# Sheet1.net
KiCad netlist of a schematic drawn in Altium Designer
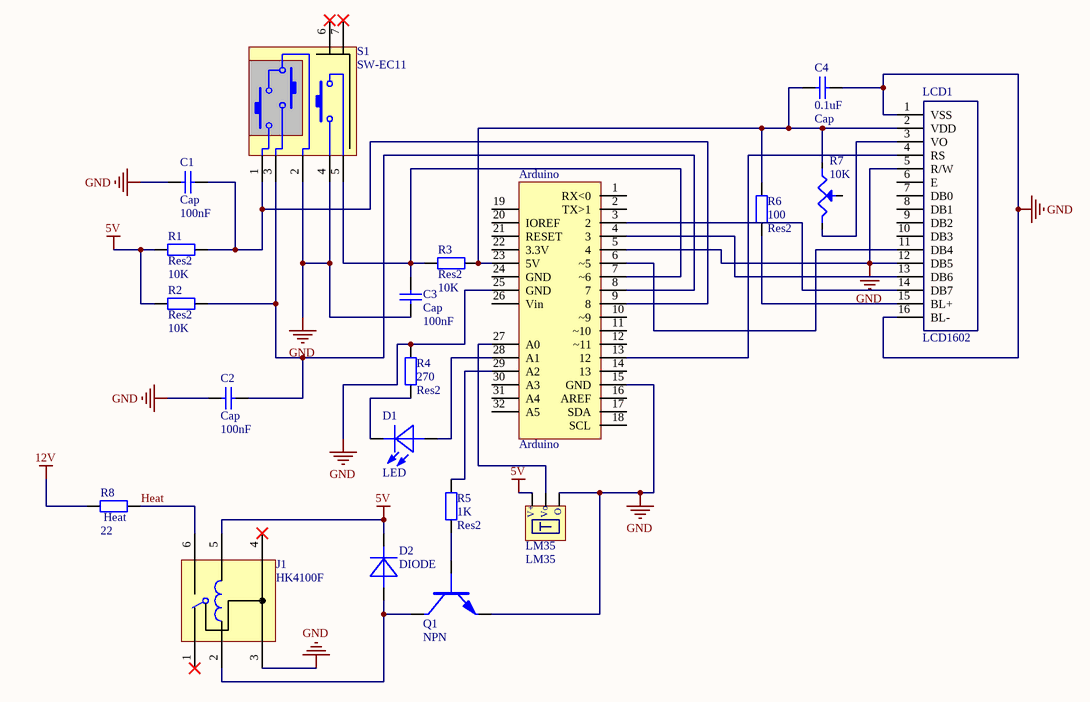
[diagram p0: Sheet1.SchDoc]

(export (version "E")
  (design (tool "Eeschema 10.0.6"))
  (components
    (comp (ref "Arduino")
      (value "Arduino")
      (footprint "Arduino-UNO")
      (libsource (lib "LixhSch") (part "Arduino-UNO"))
    )
    (comp (ref "C1")
      (value "Cap")
      (footprint "RAD-0.3")
      (description "Capacitor")
      (fields (field (name "ALTIUM_VALUE") "100nF") (field (name "PUBLISHER") "Altium Limited"))
      (libsource (lib "Miscellaneous Devices") (part "Cap"))
    )
    (comp (ref "C2")
      (value "Cap")
      (footprint "RAD-0.3")
      (description "Capacitor")
      (fields (field (name "ALTIUM_VALUE") "100nF") (field (name "PUBLISHER") "Altium Limited"))
      (libsource (lib "Miscellaneous Devices") (part "Cap"))
    )
    (comp (ref "C3")
      (value "Cap")
      (footprint "RAD-0.3")
      (description "Capacitor")
      (fields (field (name "ALTIUM_VALUE") "100nF") (field (name "PUBLISHER") "Altium Limited"))
      (libsource (lib "Miscellaneous Devices") (part "Cap"))
    )
    (comp (ref "C4")
      (value "Cap")
      (footprint "RAD-0.3")
      (description "Capacitor")
      (fields (field (name "ALTIUM_VALUE") "0.1uF") (field (name "PUBLISHER") "Altium Limited"))
      (libsource (lib "Miscellaneous Devices") (part "Cap"))
    )
    (comp (ref "D1")
      (value "LED")
      (footprint "LEDLXH-5")
      (description "发光二极管")
      (libsource (lib "LixhSch") (part "LEDLXH"))
    )
    (comp (ref "D2")
      (value "DIODE")
      (footprint "DIODE-4")
      (description "Diode")
      (libsource (lib "LixhSch") (part "DIODELXH"))
    )
    (comp (ref "J1")
      (value "HK4100F")
      (footprint "HK4100F")
      (description "单刀双掷继电器")
      (libsource (lib "Fszhang") (part "HK4100F"))
    )
    (comp (ref "LCD1") (value "LCD1602") (footprint "LCD1602") (libsource (lib "LCD") (part "LCD1602")))
    (comp (ref "LM35")
      (value "LM35")
      (footprint "LM35")
      (description "LM35温度传感器")
      (libsource (lib "LixhSch") (part "LM35"))
    )
    (comp (ref "Q1")
      (value "NPN")
      (footprint "NPN")
      (description "NPN Transistor")
      (libsource (lib "LixhSch") (part "NPNLXH"))
    )
    (comp (ref "R1")
      (value "Res2")
      (footprint "AXIAL-0.4")
      (description "Resistor")
      (fields (field (name "ALTIUM_VALUE") "10K") (field (name "PUBLISHER") "Altium Limited"))
      (libsource (lib "") (part "Res2_1"))
    )
    (comp (ref "R2")
      (value "Res2")
      (footprint "AXIAL-0.4")
      (description "Resistor")
      (fields (field (name "ALTIUM_VALUE") "10K") (field (name "PUBLISHER") "Altium Limited"))
      (libsource (lib "") (part "Res2_1"))
    )
    (comp (ref "R3")
      (value "Res2")
      (footprint "AXIAL-0.4")
      (description "Resistor")
      (fields (field (name "ALTIUM_VALUE") "10K") (field (name "PUBLISHER") "Altium Limited"))
      (libsource (lib "") (part "Res2_1"))
    )
    (comp (ref "R4")
      (value "Res2")
      (footprint "AXIAL-0.4")
      (description "Resistor")
      (fields (field (name "ALTIUM_VALUE") "270") (field (name "PUBLISHER") "Altium Limited"))
      (libsource (lib "Miscellaneous Devices") (part "Res2"))
    )
    (comp (ref "R5")
      (value "Res2")
      (footprint "AXIAL-0.4")
      (description "Resistor")
      (fields (field (name "ALTIUM_VALUE") "1K") (field (name "PUBLISHER") "Altium Limited"))
      (libsource (lib "Miscellaneous Devices") (part "Res2"))
    )
    (comp (ref "R6")
      (value "Res2")
      (footprint "AXIAL-0.4")
      (description "Resistor")
      (fields (field (name "ALTIUM_VALUE") "100") (field (name "PUBLISHER") "Altium Limited"))
      (libsource (lib "Miscellaneous Devices") (part "Res2"))
    )
    (comp (ref "R7")
      (value "10K")
      (footprint "VR-5")
      (description "Potentiometer")
      (libsource (lib "Miscellaneous Devices") (part "POT1"))
    )
    (comp (ref "R8")
      (value "Heat")
      (footprint "AXIAL-0.4")
      (description "Resistor")
      (fields (field (name "ALTIUM_VALUE") "22") (field (name "PUBLISHER") "Altium Limited"))
      (libsource (lib "") (part "Res2_2"))
    )
    (comp (ref "S1")
      (value "SW-EC11")
      (footprint "EC11")
      (description "旋转编码开关")
      (fields (field (name "PUBLISHER") "Altium Limited"))
      (libsource (lib "LixhSch") (part "SW-EC11"))
    )
  )
  (nets
    (net (code "1") (name "/Heat") (class "Default")
      (node (ref "J1") (pin "6") (pinfunction "6_6") (pintype "passive"))
      (node (ref "R8") (pin "1") (pinfunction "1_1") (pintype "passive"))
    )
    (net (code "2") (name "5V") (class "Default")
      (node (ref "D2") (pin "2") (pinfunction "K_2") (pintype "passive"))
      (node (ref "J1") (pin "5") (pinfunction "5_5") (pintype "passive"))
      (node (ref "LM35") (pin "1") (pinfunction "1_1") (pintype "power_in"))
      (node (ref "R1") (pin "1") (pinfunction "1_1") (pintype "passive"))
      (node (ref "R2") (pin "1") (pinfunction "1_1") (pintype "passive"))
    )
    (net (code "3") (name "12V") (class "Default")
      (node (ref "R8") (pin "2") (pinfunction "2_2") (pintype "passive"))
    )
    (net (code "4") (name "GND") (class "Default")
      (node (ref "Arduino") (pin "15") (pinfunction "GND_15") (pintype "power_in"))
      (node (ref "Arduino") (pin "25") (pinfunction "GND_25") (pintype "power_in"))
      (node (ref "Arduino") (pin "5") (pinfunction "4_5") (pintype "power_in"))
      (node (ref "C1") (pin "2") (pinfunction "2_2") (pintype "passive"))
      (node (ref "C2") (pin "2") (pinfunction "2_2") (pintype "passive"))
      (node (ref "C3") (pin "1") (pinfunction "1_1") (pintype "passive"))
      (node (ref "C4") (pin "1") (pinfunction "1_1") (pintype "passive"))
      (node (ref "J1") (pin "3") (pinfunction "3_3") (pintype "passive"))
      (node (ref "LCD1") (pin "1") (pinfunction "VSS_1") (pintype "passive"))
      (node (ref "LCD1") (pin "12") (pinfunction "DB5_12") (pintype "passive"))
      (node (ref "LCD1") (pin "16") (pinfunction "BL-_16") (pintype "passive"))
      (node (ref "LCD1") (pin "5") (pinfunction "R/W_5") (pintype "passive"))
      (node (ref "LM35") (pin "3") (pinfunction "3_3") (pintype "power_in"))
      (node (ref "Q1") (pin "1") (pinfunction "E_1") (pintype "passive"))
      (node (ref "R4") (pin "2") (pinfunction "2_2") (pintype "passive"))
      (node (ref "S1") (pin "2") (pinfunction "2_2") (pintype "passive"))
      (node (ref "S1") (pin "4") (pinfunction "4_4") (pintype "passive"))
    )
    (net (code "5") (name "Net-(Arduino-2)") (class "Default")
      (node (ref "Arduino") (pin "3") (pinfunction "2_3") (pintype "power_in"))
      (node (ref "LCD1") (pin "14") (pinfunction "DB7_14") (pintype "passive"))
    )
    (net (code "6") (name "Net-(Arduino-3)") (class "Default")
      (node (ref "Arduino") (pin "4") (pinfunction "3_4") (pintype "power_in"))
      (node (ref "LCD1") (pin "13") (pinfunction "DB6_13") (pintype "passive"))
    )
    (net (code "7") (name "Net-(Arduino-5V)") (class "Default")
      (node (ref "Arduino") (pin "23") (pinfunction "5V_23") (pintype "power_in"))
      (node (ref "C4") (pin "2") (pinfunction "2_2") (pintype "passive"))
      (node (ref "LCD1") (pin "2") (pinfunction "VDD_2") (pintype "passive"))
      (node (ref "R3") (pin "2") (pinfunction "2_2") (pintype "passive"))
      (node (ref "R6") (pin "2") (pinfunction "2_2") (pintype "passive"))
      (node (ref "R7") (pin "1") (pinfunction "1_1") (pintype "passive"))
    )
    (net (code "8") (name "Net-(Arduino-7)") (class "Default")
      (node (ref "Arduino") (pin "8") (pinfunction "7_8") (pintype "power_in"))
      (node (ref "C2") (pin "1") (pinfunction "1_1") (pintype "passive"))
      (node (ref "R2") (pin "2") (pinfunction "2_2") (pintype "passive"))
      (node (ref "S1") (pin "3") (pinfunction "3_3") (pintype "passive"))
    )
    (net (code "9") (name "Net-(Arduino-8)") (class "Default")
      (node (ref "Arduino") (pin "9") (pinfunction "8_9") (pintype "power_in"))
      (node (ref "C1") (pin "1") (pinfunction "1_1") (pintype "passive"))
      (node (ref "R1") (pin "2") (pinfunction "2_2") (pintype "passive"))
      (node (ref "S1") (pin "1") (pinfunction "1_1") (pintype "passive"))
    )
    (net (code "10") (name "Net-(Arduino-12)") (class "Default")
      (node (ref "Arduino") (pin "13") (pinfunction "12_13") (pintype "power_in"))
      (node (ref "LCD1") (pin "4") (pinfunction "RS_4") (pintype "passive"))
    )
    (net (code "11") (name "Net-(Arduino-A0)") (class "Default")
      (node (ref "Arduino") (pin "27") (pinfunction "A0_27") (pintype "power_in"))
      (node (ref "LM35") (pin "2") (pinfunction "2_2") (pintype "passive"))
    )
    (net (code "12") (name "Net-(Arduino-A1)") (class "Default")
      (node (ref "Arduino") (pin "28") (pinfunction "A1_28") (pintype "power_in"))
      (node (ref "D1") (pin "1") (pinfunction "A_1") (pintype "passive"))
    )
    (net (code "13") (name "Net-(Arduino-A2)") (class "Default")
      (node (ref "Arduino") (pin "29") (pinfunction "A2_29") (pintype "power_in"))
      (node (ref "R5") (pin "2") (pinfunction "2_2") (pintype "passive"))
    )
    (net (code "14") (name "Net-(Arduino-~5)") (class "Default")
      (node (ref "Arduino") (pin "6") (pinfunction "~5_6") (pintype "power_in"))
      (node (ref "LCD1") (pin "11") (pinfunction "DB4_11") (pintype "passive"))
    )
    (net (code "15") (name "Net-(Arduino-~6)") (class "Default")
      (node (ref "Arduino") (pin "7") (pinfunction "~6_7") (pintype "power_in"))
      (node (ref "C3") (pin "2") (pinfunction "2_2") (pintype "passive"))
      (node (ref "R3") (pin "1") (pinfunction "1_1") (pintype "passive"))
      (node (ref "S1") (pin "5") (pinfunction "5_5") (pintype "passive"))
    )
    (net (code "16") (name "Net-(D1-K)") (class "Default")
      (node (ref "D1") (pin "2") (pinfunction "K_2") (pintype "passive"))
      (node (ref "R4") (pin "1") (pinfunction "1_1") (pintype "passive"))
    )
    (net (code "17") (name "Net-(D2-A)") (class "Default")
      (node (ref "D2") (pin "1") (pinfunction "A_1") (pintype "passive"))
      (node (ref "J1") (pin "2") (pinfunction "2_2") (pintype "passive"))
      (node (ref "Q1") (pin "3") (pinfunction "C_3") (pintype "passive"))
    )
    (net (code "18") (name "Net-(LCD1-BL+)") (class "Default")
      (node (ref "LCD1") (pin "15") (pinfunction "BL+_15") (pintype "passive"))
      (node (ref "R6") (pin "1") (pinfunction "1_1") (pintype "passive"))
    )
    (net (code "19") (name "Net-(LCD1-VO)") (class "Default")
      (node (ref "LCD1") (pin "3") (pinfunction "VO_3") (pintype "passive"))
      (node (ref "R7") (pin "2") (pinfunction "2_2") (pintype "passive"))
    )
    (net (code "20") (name "Net-(Q1-B)") (class "Default")
      (node (ref "Q1") (pin "2") (pinfunction "B_2") (pintype "passive"))
      (node (ref "R5") (pin "1") (pinfunction "1_1") (pintype "passive"))
    )
    (net (code "21") (name "unconnected-(Arduino-3.3V-Pad22)") (class "Default")
      (node (ref "Arduino") (pin "22") (pinfunction "3.3V_22") (pintype "power_in"))
    )
    (net (code "22") (name "unconnected-(Arduino-13-Pad14)") (class "Default")
      (node (ref "Arduino") (pin "14") (pinfunction "13_14") (pintype "power_in"))
    )
    (net (code "23") (name "unconnected-(Arduino-A3-Pad30)") (class "Default")
      (node (ref "Arduino") (pin "30") (pinfunction "A3_30") (pintype "power_in"))
    )
    (net (code "24") (name "unconnected-(Arduino-A4-Pad31)") (class "Default")
      (node (ref "Arduino") (pin "31") (pinfunction "A4_31") (pintype "power_in"))
    )
    (net (code "25") (name "unconnected-(Arduino-A5-Pad32)") (class "Default")
      (node (ref "Arduino") (pin "32") (pinfunction "A5_32") (pintype "power_in"))
    )
    (net (code "26") (name "unconnected-(Arduino-AREF-Pad16)") (class "Default")
      (node (ref "Arduino") (pin "16") (pinfunction "AREF_16") (pintype "power_in"))
    )
    (net (code "27") (name "unconnected-(Arduino-GND-Pad24)") (class "Default")
      (node (ref "Arduino") (pin "24") (pinfunction "GND_24") (pintype "power_in"))
    )
    (net (code "28") (name "unconnected-(Arduino-IOREF-Pad20)") (class "Default")
      (node (ref "Arduino") (pin "20") (pinfunction "IOREF_20") (pintype "power_in"))
    )
    (net (code "29") (name "unconnected-(Arduino-Pad19)") (class "Default")
      (node (ref "Arduino") (pin "19") (pintype "power_in"))
    )
    (net (code "30") (name "unconnected-(Arduino-RESET-Pad21)") (class "Default")
      (node (ref "Arduino") (pin "21") (pinfunction "RESET_21") (pintype "power_in"))
    )
    (net (code "31") (name "unconnected-(Arduino-RX<0-Pad1)") (class "Default")
      (node (ref "Arduino") (pin "1") (pinfunction "RX<0_1") (pintype "power_in"))
    )
    (net (code "32") (name "unconnected-(Arduino-SCL-Pad18)") (class "Default")
      (node (ref "Arduino") (pin "18") (pinfunction "SCL_18") (pintype "power_in"))
    )
    (net (code "33") (name "unconnected-(Arduino-SDA-Pad17)") (class "Default")
      (node (ref "Arduino") (pin "17") (pinfunction "SDA_17") (pintype "power_in"))
    )
    (net (code "34") (name "unconnected-(Arduino-TX>1-Pad2)") (class "Default")
      (node (ref "Arduino") (pin "2") (pinfunction "TX>1_2") (pintype "power_in"))
    )
    (net (code "35") (name "unconnected-(Arduino-Vin-Pad26)") (class "Default")
      (node (ref "Arduino") (pin "26") (pinfunction "Vin_26") (pintype "power_in"))
    )
    (net (code "36") (name "unconnected-(Arduino-~9-Pad10)") (class "Default")
      (node (ref "Arduino") (pin "10") (pinfunction "~9_10") (pintype "power_in"))
    )
    (net (code "37") (name "unconnected-(Arduino-~10-Pad11)") (class "Default")
      (node (ref "Arduino") (pin "11") (pinfunction "~10_11") (pintype "power_in"))
    )
    (net (code "38") (name "unconnected-(Arduino-~11-Pad12)") (class "Default")
      (node (ref "Arduino") (pin "12") (pinfunction "~11_12") (pintype "power_in"))
    )
    (net (code "39") (name "unconnected-(J1-Pad1)") (class "Default")
      (node (ref "J1") (pin "1") (pinfunction "1_1") (pintype "passive+no_connect"))
    )
    (net (code "40") (name "unconnected-(J1-Pad4)") (class "Default")
      (node (ref "J1") (pin "4") (pinfunction "4_4") (pintype "passive+no_connect"))
    )
    (net (code "41") (name "unconnected-(LCD1-DB0-Pad7)") (class "Default")
      (node (ref "LCD1") (pin "7") (pinfunction "DB0_7") (pintype "passive"))
    )
    (net (code "42") (name "unconnected-(LCD1-DB1-Pad8)") (class "Default")
      (node (ref "LCD1") (pin "8") (pinfunction "DB1_8") (pintype "passive"))
    )
    (net (code "43") (name "unconnected-(LCD1-DB2-Pad9)") (class "Default")
      (node (ref "LCD1") (pin "9") (pinfunction "DB2_9") (pintype "passive"))
    )
    (net (code "44") (name "unconnected-(LCD1-DB3-Pad10)") (class "Default")
      (node (ref "LCD1") (pin "10") (pinfunction "DB3_10") (pintype "passive"))
    )
    (net (code "45") (name "unconnected-(LCD1-E-Pad6)") (class "Default")
      (node (ref "LCD1") (pin "6") (pinfunction "E_6") (pintype "passive"))
    )
    (net (code "46") (name "unconnected-(R7-W-Pad3)") (class "Default")
      (node (ref "R7") (pin "3") (pinfunction "W_3") (pintype "passive"))
    )
    (net (code "47") (name "unconnected-(S1-Pad6)") (class "Default")
      (node (ref "S1") (pin "6") (pinfunction "6_6") (pintype "passive+no_connect"))
    )
    (net (code "48") (name "unconnected-(S1-Pad7)") (class "Default")
      (node (ref "S1") (pin "7") (pinfunction "7_7") (pintype "passive+no_connect"))
    )
  )
)
